# RS485_Com_and_Connectors.net
KiCad netlist of a schematic drawn in Altium Designer
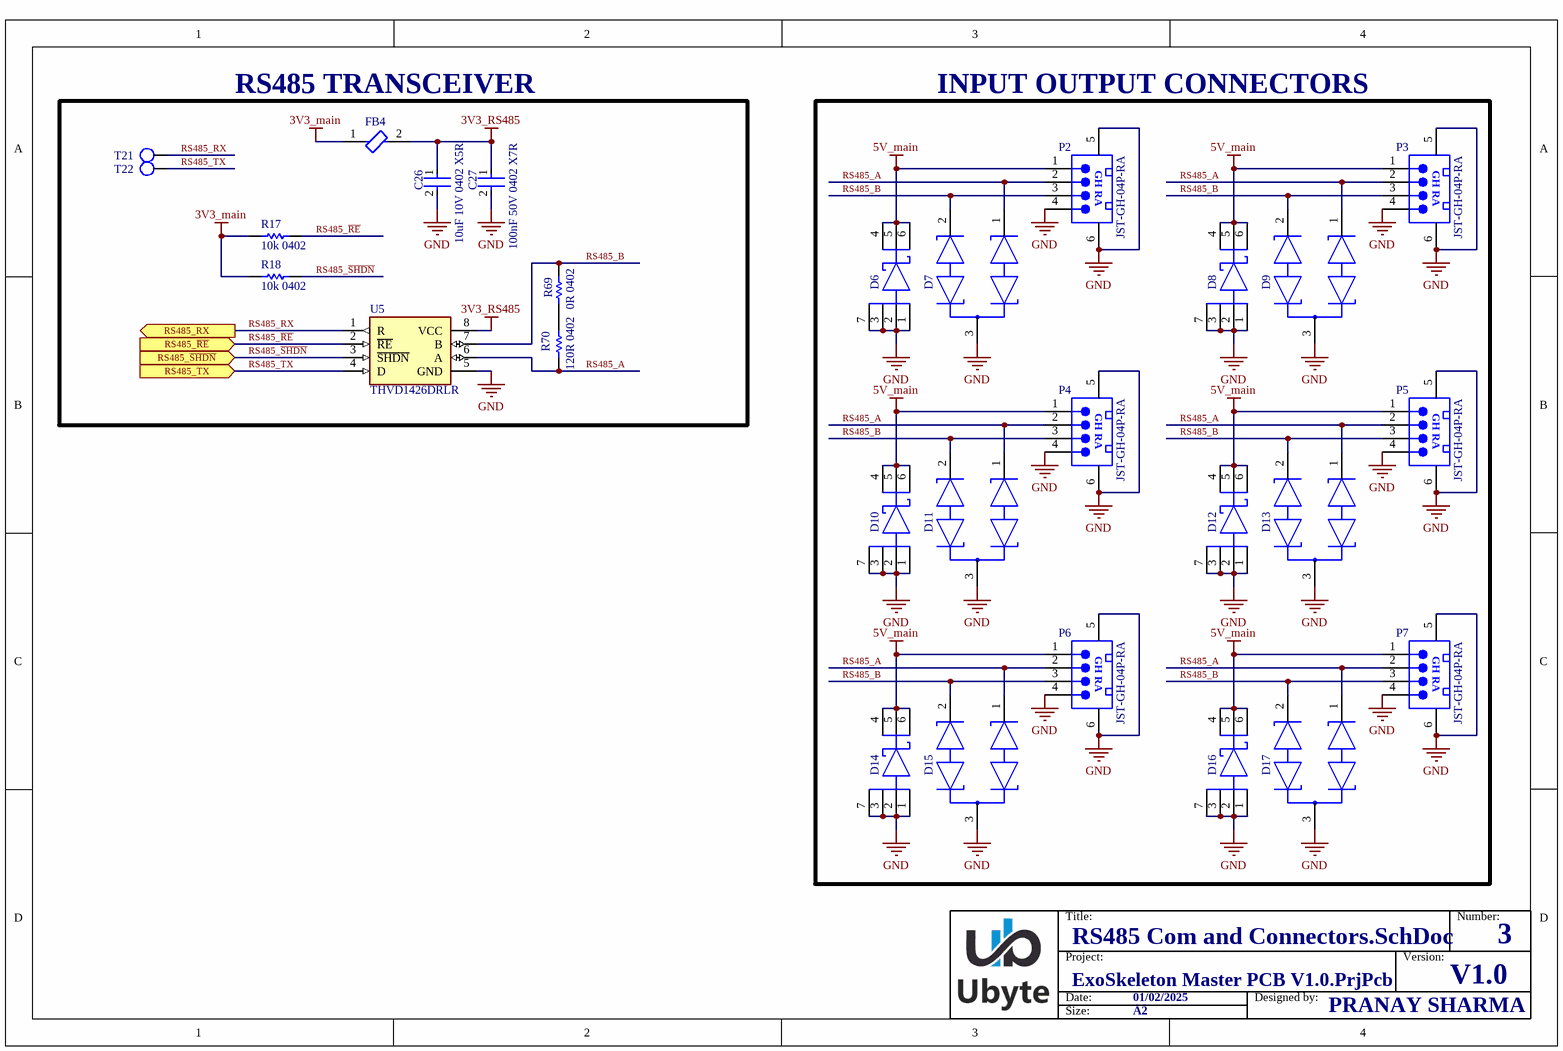
[diagram p0: RS485 Com and Connectors.SchDoc]

(export (version "E")
  (design (tool "Eeschema 10.0.6"))
  (components
    (comp (ref "C26")
      (value "10uF 10V 0402 X5R")
      (footprint "Res, Cap, Ind, LED, FB_Lib:0402 IPC CLASS C CAPACITOR")
      (libsource (lib "Capacitor_Lib") (part "10uF 10V 0402 X5R"))
    )
    (comp (ref "C27")
      (value "100nF 50V 0402 X7R")
      (footprint "Res, Cap, Ind, LED, FB_Lib:0402 IPC CLASS C CAPACITOR")
      (libsource (lib "Capacitor_Lib") (part "100nF 50V 0402 X7R"))
    )
    (comp (ref "D6")
      (value "~")
      (footprint "Res, Cap, Ind, LED, FB_Lib:DRV0006A IPC-C")
      (libsource (lib "Diodes_Lib") (part "TVS0500DRVR"))
    )
    (comp (ref "D7")
      (value "~")
      (footprint "Res, Cap, Ind, LED, FB_Lib:FP-SOT23-IPC_C")
      (libsource (lib "Diodes_Lib") (part "SM712"))
    )
    (comp (ref "D8")
      (value "~")
      (footprint "Res, Cap, Ind, LED, FB_Lib:DRV0006A IPC-C")
      (libsource (lib "Diodes_Lib") (part "TVS0500DRVR"))
    )
    (comp (ref "D9")
      (value "~")
      (footprint "Res, Cap, Ind, LED, FB_Lib:FP-SOT23-IPC_C")
      (libsource (lib "Diodes_Lib") (part "SM712"))
    )
    (comp (ref "D10")
      (value "~")
      (footprint "Res, Cap, Ind, LED, FB_Lib:DRV0006A IPC-C")
      (libsource (lib "Diodes_Lib") (part "TVS0500DRVR"))
    )
    (comp (ref "D11")
      (value "~")
      (footprint "Res, Cap, Ind, LED, FB_Lib:FP-SOT23-IPC_C")
      (libsource (lib "Diodes_Lib") (part "SM712"))
    )
    (comp (ref "D12")
      (value "~")
      (footprint "Res, Cap, Ind, LED, FB_Lib:DRV0006A IPC-C")
      (libsource (lib "Diodes_Lib") (part "TVS0500DRVR"))
    )
    (comp (ref "D13")
      (value "~")
      (footprint "Res, Cap, Ind, LED, FB_Lib:FP-SOT23-IPC_C")
      (libsource (lib "Diodes_Lib") (part "SM712"))
    )
    (comp (ref "D14")
      (value "~")
      (footprint "Res, Cap, Ind, LED, FB_Lib:DRV0006A IPC-C")
      (libsource (lib "Diodes_Lib") (part "TVS0500DRVR"))
    )
    (comp (ref "D15")
      (value "~")
      (footprint "Res, Cap, Ind, LED, FB_Lib:FP-SOT23-IPC_C")
      (libsource (lib "Diodes_Lib") (part "SM712"))
    )
    (comp (ref "D16")
      (value "~")
      (footprint "Res, Cap, Ind, LED, FB_Lib:DRV0006A IPC-C")
      (libsource (lib "Diodes_Lib") (part "TVS0500DRVR"))
    )
    (comp (ref "D17")
      (value "~")
      (footprint "Res, Cap, Ind, LED, FB_Lib:FP-SOT23-IPC_C")
      (libsource (lib "Diodes_Lib") (part "SM712"))
    )
    (comp (ref "FB4")
      (value "BLM15AX102SN1D")
      (footprint "Res, Cap, Ind, LED, FB_Lib:0402 IPC CLASS C FERRITE BEAD")
      (libsource (lib "Ferrite_Bead_Lib") (part "BLM15AX102SN1D"))
    )
    (comp (ref "P2")
      (value "JST-GH-04P-RA")
      (footprint "Connectors_Lib:JST-GH-04P-RA")
      (libsource (lib "Connectors_Lib") (part "JST-GH-04P-RA"))
    )
    (comp (ref "P3")
      (value "JST-GH-04P-RA")
      (footprint "Connectors_Lib:JST-GH-04P-RA")
      (libsource (lib "Connectors_Lib") (part "JST-GH-04P-RA"))
    )
    (comp (ref "P4")
      (value "JST-GH-04P-RA")
      (footprint "Connectors_Lib:JST-GH-04P-RA")
      (libsource (lib "Connectors_Lib") (part "JST-GH-04P-RA"))
    )
    (comp (ref "P5")
      (value "JST-GH-04P-RA")
      (footprint "Connectors_Lib:JST-GH-04P-RA")
      (libsource (lib "Connectors_Lib") (part "JST-GH-04P-RA"))
    )
    (comp (ref "P6")
      (value "JST-GH-04P-RA")
      (footprint "Connectors_Lib:JST-GH-04P-RA")
      (libsource (lib "Connectors_Lib") (part "JST-GH-04P-RA"))
    )
    (comp (ref "P7")
      (value "JST-GH-04P-RA")
      (footprint "Connectors_Lib:JST-GH-04P-RA")
      (libsource (lib "Connectors_Lib") (part "JST-GH-04P-RA"))
    )
    (comp (ref "R17")
      (value "10k 0402")
      (footprint "Res, Cap, Ind, LED, FB_Lib:0402 IPC CLASS C RESISTOR")
      (libsource (lib "Resistor_Lib") (part "10k 1% 0402"))
    )
    (comp (ref "R18")
      (value "10k 0402")
      (footprint "Res, Cap, Ind, LED, FB_Lib:0402 IPC CLASS C RESISTOR")
      (libsource (lib "Resistor_Lib") (part "10k 1% 0402"))
    )
    (comp (ref "R69")
      (value "0R 0402")
      (footprint "Res, Cap, Ind, LED, FB_Lib:0402 IPC CLASS B RESISTOR")
      (libsource (lib "Resistor_Lib") (part "0R 1% 0402"))
    )
    (comp (ref "R70")
      (value "120R 0402")
      (footprint "Res, Cap, Ind, LED, FB_Lib:0402 IPC CLASS C RESISTOR")
      (libsource (lib "Resistor_Lib") (part "120R 1% 0402"))
    )
    (comp (ref "T21")
      (value "TP")
      (footprint "Miscellaneous_Lib:Testpoint1")
      (libsource (lib "Miscellaneous_Lib") (part "Testpoint1"))
    )
    (comp (ref "T22")
      (value "TP")
      (footprint "Miscellaneous_Lib:Testpoint1")
      (libsource (lib "Miscellaneous_Lib") (part "Testpoint1"))
    )
    (comp (ref "U5")
      (value "THVD1426DRLR")
      (footprint "Integrated_Circuits_Lib:DRL0008A IPC-C")
      (libsource (lib "Integrated_Circuits_Lib") (part "THVD1426DRLR"))
    )
  )
  (nets
    (net (code "1") (name "/RS485_A") (class "Default")
      (node (ref "D11") (pin "1") (pinfunction "K1_1") (pintype "passive"))
      (node (ref "D13") (pin "1") (pinfunction "K1_1") (pintype "passive"))
      (node (ref "D15") (pin "1") (pinfunction "K1_1") (pintype "passive"))
      (node (ref "D17") (pin "1") (pinfunction "K1_1") (pintype "passive"))
      (node (ref "D7") (pin "1") (pinfunction "K1_1") (pintype "passive"))
      (node (ref "D9") (pin "1") (pinfunction "K1_1") (pintype "passive"))
      (node (ref "P2") (pin "2") (pinfunction "2_2") (pintype "passive"))
      (node (ref "P3") (pin "2") (pinfunction "2_2") (pintype "passive"))
      (node (ref "P4") (pin "2") (pinfunction "2_2") (pintype "passive"))
      (node (ref "P5") (pin "2") (pinfunction "2_2") (pintype "passive"))
      (node (ref "P6") (pin "2") (pinfunction "2_2") (pintype "passive"))
      (node (ref "P7") (pin "2") (pinfunction "2_2") (pintype "passive"))
      (node (ref "R70") (pin "1") (pinfunction "1_1") (pintype "passive"))
      (node (ref "U5") (pin "6") (pinfunction "A_6") (pintype "bidirectional"))
    )
    (net (code "2") (name "/RS485_B") (class "Default")
      (node (ref "D11") (pin "2") (pinfunction "K2_2") (pintype "passive"))
      (node (ref "D13") (pin "2") (pinfunction "K2_2") (pintype "passive"))
      (node (ref "D15") (pin "2") (pinfunction "K2_2") (pintype "passive"))
      (node (ref "D17") (pin "2") (pinfunction "K2_2") (pintype "passive"))
      (node (ref "D7") (pin "2") (pinfunction "K2_2") (pintype "passive"))
      (node (ref "D9") (pin "2") (pinfunction "K2_2") (pintype "passive"))
      (node (ref "P2") (pin "3") (pinfunction "3_3") (pintype "passive"))
      (node (ref "P3") (pin "3") (pinfunction "3_3") (pintype "passive"))
      (node (ref "P4") (pin "3") (pinfunction "3_3") (pintype "passive"))
      (node (ref "P5") (pin "3") (pinfunction "3_3") (pintype "passive"))
      (node (ref "P6") (pin "3") (pinfunction "3_3") (pintype "passive"))
      (node (ref "P7") (pin "3") (pinfunction "3_3") (pintype "passive"))
      (node (ref "R69") (pin "2") (pinfunction "2_2") (pintype "passive"))
      (node (ref "U5") (pin "7") (pinfunction "B_7") (pintype "bidirectional"))
    )
    (net (code "3") (name "/RS485_RX") (class "Default")
      (node (ref "T21") (pin "0") (pinfunction "0_0") (pintype "passive"))
      (node (ref "U5") (pin "1") (pinfunction "R_1") (pintype "output"))
    )
    (net (code "4") (name "/RS485_TX") (class "Default")
      (node (ref "T22") (pin "0") (pinfunction "0_0") (pintype "passive"))
      (node (ref "U5") (pin "4") (pinfunction "D_4") (pintype "input"))
    )
    (net (code "5") (name "/RS485_~{RE}") (class "Default")
      (node (ref "R17") (pin "1") (pinfunction "1_1") (pintype "passive"))
      (node (ref "U5") (pin "2") (pinfunction "~{RE}_2") (pintype "input"))
    )
    (net (code "6") (name "/RS485_~{SHDN}") (class "Default")
      (node (ref "R18") (pin "1") (pinfunction "1_1") (pintype "passive"))
      (node (ref "U5") (pin "3") (pinfunction "~{SHDN}_3") (pintype "input"))
    )
    (net (code "7") (name "3V3_RS485") (class "Default")
      (node (ref "C26") (pin "1") (pinfunction "1_1") (pintype "passive"))
      (node (ref "C27") (pin "1") (pinfunction "1_1") (pintype "passive"))
      (node (ref "FB4") (pin "2") (pinfunction "2_2") (pintype "passive"))
      (node (ref "U5") (pin "8") (pinfunction "VCC_8") (pintype "power_in"))
    )
    (net (code "8") (name "3V3_main") (class "Default")
      (node (ref "FB4") (pin "1") (pinfunction "1_1") (pintype "passive"))
      (node (ref "R17") (pin "2") (pinfunction "2_2") (pintype "passive"))
      (node (ref "R18") (pin "2") (pinfunction "2_2") (pintype "passive"))
    )
    (net (code "9") (name "5V_main") (class "Default")
      (node (ref "D10") (pin "4") (pinfunction "4_4") (pintype "passive"))
      (node (ref "D10") (pin "5") (pinfunction "5_5") (pintype "passive"))
      (node (ref "D10") (pin "6") (pinfunction "6_6") (pintype "passive"))
      (node (ref "D12") (pin "4") (pinfunction "4_4") (pintype "passive"))
      (node (ref "D12") (pin "5") (pinfunction "5_5") (pintype "passive"))
      (node (ref "D12") (pin "6") (pinfunction "6_6") (pintype "passive"))
      (node (ref "D14") (pin "4") (pinfunction "4_4") (pintype "passive"))
      (node (ref "D14") (pin "5") (pinfunction "5_5") (pintype "passive"))
      (node (ref "D14") (pin "6") (pinfunction "6_6") (pintype "passive"))
      (node (ref "D16") (pin "4") (pinfunction "4_4") (pintype "passive"))
      (node (ref "D16") (pin "5") (pinfunction "5_5") (pintype "passive"))
      (node (ref "D16") (pin "6") (pinfunction "6_6") (pintype "passive"))
      (node (ref "D6") (pin "4") (pinfunction "4_4") (pintype "passive"))
      (node (ref "D6") (pin "5") (pinfunction "5_5") (pintype "passive"))
      (node (ref "D6") (pin "6") (pinfunction "6_6") (pintype "passive"))
      (node (ref "D8") (pin "4") (pinfunction "4_4") (pintype "passive"))
      (node (ref "D8") (pin "5") (pinfunction "5_5") (pintype "passive"))
      (node (ref "D8") (pin "6") (pinfunction "6_6") (pintype "passive"))
      (node (ref "P2") (pin "1") (pinfunction "1_1") (pintype "passive"))
      (node (ref "P3") (pin "1") (pinfunction "1_1") (pintype "passive"))
      (node (ref "P4") (pin "1") (pinfunction "1_1") (pintype "passive"))
      (node (ref "P5") (pin "1") (pinfunction "1_1") (pintype "passive"))
      (node (ref "P6") (pin "1") (pinfunction "1_1") (pintype "passive"))
      (node (ref "P7") (pin "1") (pinfunction "1_1") (pintype "passive"))
    )
    (net (code "10") (name "GND") (class "Default")
      (node (ref "C26") (pin "2") (pinfunction "2_2") (pintype "passive"))
      (node (ref "C27") (pin "2") (pinfunction "2_2") (pintype "passive"))
      (node (ref "D10") (pin "1") (pinfunction "C_1") (pintype "passive"))
      (node (ref "D10") (pin "2") (pinfunction "A_2") (pintype "passive"))
      (node (ref "D10") (pin "3") (pinfunction "3_3") (pintype "passive"))
      (node (ref "D10") (pin "7") (pinfunction "7_7") (pintype "passive"))
      (node (ref "D11") (pin "3") (pinfunction "CC_3") (pintype "passive"))
      (node (ref "D12") (pin "1") (pinfunction "C_1") (pintype "passive"))
      (node (ref "D12") (pin "2") (pinfunction "A_2") (pintype "passive"))
      (node (ref "D12") (pin "3") (pinfunction "3_3") (pintype "passive"))
      (node (ref "D12") (pin "7") (pinfunction "7_7") (pintype "passive"))
      (node (ref "D13") (pin "3") (pinfunction "CC_3") (pintype "passive"))
      (node (ref "D14") (pin "1") (pinfunction "C_1") (pintype "passive"))
      (node (ref "D14") (pin "2") (pinfunction "A_2") (pintype "passive"))
      (node (ref "D14") (pin "3") (pinfunction "3_3") (pintype "passive"))
      (node (ref "D14") (pin "7") (pinfunction "7_7") (pintype "passive"))
      (node (ref "D15") (pin "3") (pinfunction "CC_3") (pintype "passive"))
      (node (ref "D16") (pin "1") (pinfunction "C_1") (pintype "passive"))
      (node (ref "D16") (pin "2") (pinfunction "A_2") (pintype "passive"))
      (node (ref "D16") (pin "3") (pinfunction "3_3") (pintype "passive"))
      (node (ref "D16") (pin "7") (pinfunction "7_7") (pintype "passive"))
      (node (ref "D17") (pin "3") (pinfunction "CC_3") (pintype "passive"))
      (node (ref "D6") (pin "1") (pinfunction "C_1") (pintype "passive"))
      (node (ref "D6") (pin "2") (pinfunction "A_2") (pintype "passive"))
      (node (ref "D6") (pin "3") (pinfunction "3_3") (pintype "passive"))
      (node (ref "D6") (pin "7") (pinfunction "7_7") (pintype "passive"))
      (node (ref "D7") (pin "3") (pinfunction "CC_3") (pintype "passive"))
      (node (ref "D8") (pin "1") (pinfunction "C_1") (pintype "passive"))
      (node (ref "D8") (pin "2") (pinfunction "A_2") (pintype "passive"))
      (node (ref "D8") (pin "3") (pinfunction "3_3") (pintype "passive"))
      (node (ref "D8") (pin "7") (pinfunction "7_7") (pintype "passive"))
      (node (ref "D9") (pin "3") (pinfunction "CC_3") (pintype "passive"))
      (node (ref "P2") (pin "4") (pinfunction "4_4") (pintype "passive"))
      (node (ref "P2") (pin "5") (pinfunction "5_5") (pintype "passive"))
      (node (ref "P2") (pin "6") (pinfunction "6_6") (pintype "passive"))
      (node (ref "P3") (pin "4") (pinfunction "4_4") (pintype "passive"))
      (node (ref "P3") (pin "5") (pinfunction "5_5") (pintype "passive"))
      (node (ref "P3") (pin "6") (pinfunction "6_6") (pintype "passive"))
      (node (ref "P4") (pin "4") (pinfunction "4_4") (pintype "passive"))
      (node (ref "P4") (pin "5") (pinfunction "5_5") (pintype "passive"))
      (node (ref "P4") (pin "6") (pinfunction "6_6") (pintype "passive"))
      (node (ref "P5") (pin "4") (pinfunction "4_4") (pintype "passive"))
      (node (ref "P5") (pin "5") (pinfunction "5_5") (pintype "passive"))
      (node (ref "P5") (pin "6") (pinfunction "6_6") (pintype "passive"))
      (node (ref "P6") (pin "4") (pinfunction "4_4") (pintype "passive"))
      (node (ref "P6") (pin "5") (pinfunction "5_5") (pintype "passive"))
      (node (ref "P6") (pin "6") (pinfunction "6_6") (pintype "passive"))
      (node (ref "P7") (pin "4") (pinfunction "4_4") (pintype "passive"))
      (node (ref "P7") (pin "5") (pinfunction "5_5") (pintype "passive"))
      (node (ref "P7") (pin "6") (pinfunction "6_6") (pintype "passive"))
      (node (ref "U5") (pin "5") (pinfunction "GND_5") (pintype "power_in"))
    )
    (net (code "11") (name "Net-(R69-Pad1)") (class "Default")
      (node (ref "R69") (pin "1") (pinfunction "1_1") (pintype "passive"))
      (node (ref "R70") (pin "2") (pinfunction "2_2") (pintype "passive"))
    )
  )
)
